# processor_main_connector.net
KiCad netlist of a schematic drawn in Altium Designer
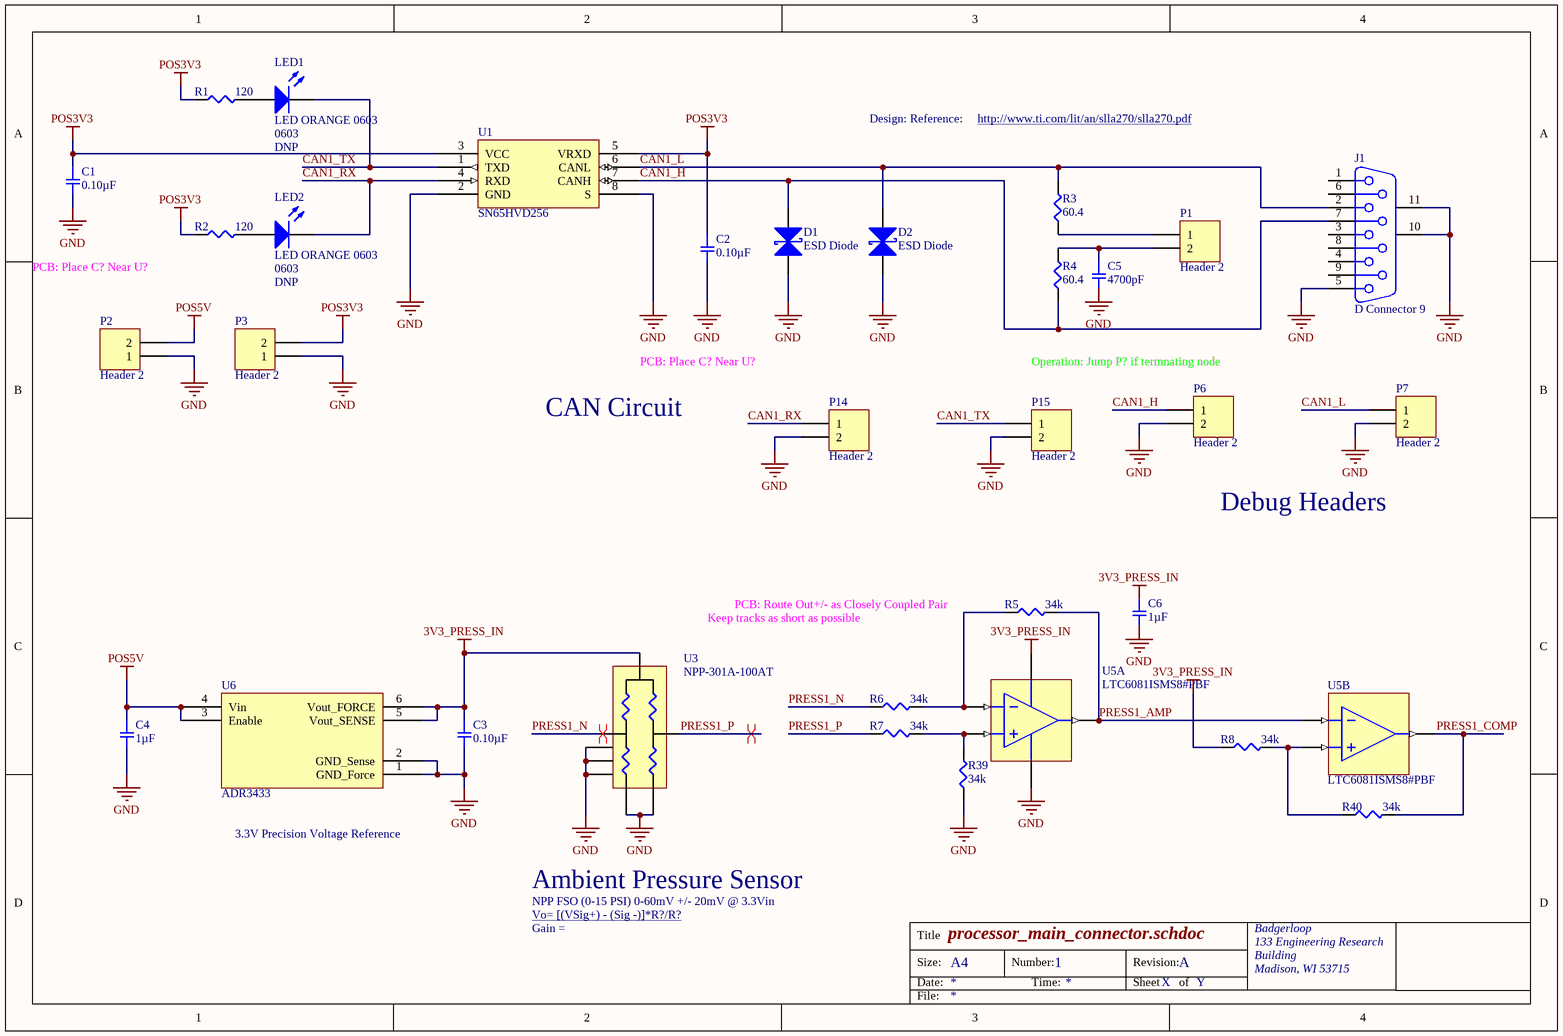
[diagram p0: processor_main_connector.SchDoc]

(export (version "E")
  (design (tool "Eeschema 10.0.6"))
  (components
    (comp (ref "C1")
      (value "0.10µF")
      (footprint "SMD-0805C")
      (description "CAP CER 0.1UF 50V X7R 0805")
      (fields
        (field (name "DIGI-KEY PART NUMBER") "490-11955-1-ND")
        (field (name "PART NUMBER") "GCD21BR71H104KA01L")
      )
      (libsource (lib "capacitor") (part "GCD21BR71H104KA01L"))
    )
    (comp (ref "C2")
      (value "0.10µF")
      (footprint "SMD-0805C")
      (description "CAP CER 0.1UF 50V X7R 0805")
      (fields
        (field (name "DIGI-KEY PART NUMBER") "490-11955-1-ND")
        (field (name "PART NUMBER") "GCD21BR71H104KA01L")
      )
      (libsource (lib "capacitor") (part "GCD21BR71H104KA01L"))
    )
    (comp (ref "C3")
      (value "0.10µF")
      (footprint "SMD-0805C")
      (description "CAP CER 0.1UF 50V X7R 0805")
      (fields
        (field (name "DIGI-KEY PART NUMBER") "490-11955-1-ND")
        (field (name "PART NUMBER") "GCD21BR71H104KA01L")
      )
      (libsource (lib "capacitor") (part "GCD21BR71H104KA01L"))
    )
    (comp (ref "C4")
      (value "1µF")
      (footprint "SMD-0805C")
      (description "CAP CER 1UF 50V X7R 0805")
      (fields
        (field (name "DIGI-KEY PART NUMBER") "490-10667-1-ND")
        (field (name "PART NUMBER") "GCJ21BR71H105KA01L")
      )
      (libsource (lib "capacitor") (part "GCJ21BR71H105KA01L"))
    )
    (comp (ref "C5")
      (value "4700pF")
      (footprint "SMD-0805C")
      (description "CAP CER 4700PF 50V NP0 0805")
      (fields
        (field (name "DIGI-KEY PART NUMBER") "490-4973-1-ND")
        (field (name "PART NUMBER") "GCM2165C1H472JA16D")
      )
      (libsource (lib "capacitor") (part "GCM2165C1H472JA16D"))
    )
    (comp (ref "C6")
      (value "1µF")
      (footprint "SMD-0805C")
      (description "CAP CER 1UF 25V X6S 0805")
      (fields
        (field (name "DIGI-KEY PART NUMBER") "490-12352-1-ND")
        (field (name "PART NUMBER") "GRT21BC81E105ME13L")
      )
      (libsource (lib "capacitor") (part "GRT21BC81E105ME13L"))
    )
    (comp (ref "D1")
      (value "ESD Diode")
      (footprint "SMD-0402-RES")
      (description "ESD Supressor")
      (fields (field (name "MANUFACTURER") "EZAEG"))
      (libsource (lib "temp") (part "ESD Diode"))
    )
    (comp (ref "D2")
      (value "ESD Diode")
      (footprint "SMD-0402-RES")
      (description "ESD Supressor")
      (fields (field (name "MANUFACTURER") "EZAEG"))
      (libsource (lib "temp") (part "ESD Diode"))
    )
    (comp (ref "J1")
      (value "D Connector 9")
      (footprint "DSUB1.385-2H9")
      (description "Receptacle Assembly, 9 Position, Right Angle")
      (fields (field (name "PUBLISHER") "Altium Limited"))
      (libsource (lib "connector") (part "D Connector 9"))
    )
    (comp (ref "LED1")
      (value "LED ORANGE 0603")
      (footprint "LED 0603 ORANGE")
      (description "A-0603UOC")
      (fields
        (field (name "MANUFACTURER") "Lighthouse LEDs")
        (field (name "PACKAGE / CASE") "0603")
        (field (name "DNP") "DNP")
      )
      (libsource (lib "misc") (part "LED ORANGE 0603"))
    )
    (comp (ref "LED2")
      (value "LED ORANGE 0603")
      (footprint "LED 0603 ORANGE")
      (description "A-0603UOC")
      (fields
        (field (name "MANUFACTURER") "Lighthouse LEDs")
        (field (name "PACKAGE / CASE") "0603")
        (field (name "DNP") "DNP")
      )
      (libsource (lib "misc") (part "LED ORANGE 0603"))
    )
    (comp (ref "P1")
      (value "Header 2")
      (footprint "Pin Header 1x2 TH Pitch 2.54mm")
      (description "Header, 2-Pin")
      (fields (field (name "PUBLISHER") "Altium Limited"))
      (libsource (lib "connector") (part "Header 2"))
    )
    (comp (ref "P2")
      (value "Header 2")
      (footprint "Pin Header 1x2 TH Pitch 2.54mm")
      (description "Header, 2-Pin")
      (fields (field (name "PUBLISHER") "Altium Limited"))
      (libsource (lib "") (part "Header 2_1"))
    )
    (comp (ref "P3")
      (value "Header 2")
      (footprint "Pin Header 1x2 TH Pitch 2.54mm")
      (description "Header, 2-Pin")
      (fields (field (name "PUBLISHER") "Altium Limited"))
      (libsource (lib "") (part "Header 2_1"))
    )
    (comp (ref "P6")
      (value "Header 2")
      (footprint "Pin Header 1x2 TH Pitch 2.54mm")
      (description "Header, 2-Pin")
      (fields (field (name "PUBLISHER") "Altium Limited"))
      (libsource (lib "connector") (part "Header 2"))
    )
    (comp (ref "P7")
      (value "Header 2")
      (footprint "Pin Header 1x2 TH Pitch 2.54mm")
      (description "Header, 2-Pin")
      (fields (field (name "PUBLISHER") "Altium Limited"))
      (libsource (lib "connector") (part "Header 2"))
    )
    (comp (ref "P14")
      (value "Header 2")
      (footprint "Pin Header 1x2 TH Pitch 2.54mm")
      (description "Header, 2-Pin")
      (fields (field (name "PUBLISHER") "Altium Limited"))
      (libsource (lib "connector") (part "Header 2"))
    )
    (comp (ref "P15")
      (value "Header 2")
      (footprint "Pin Header 1x2 TH Pitch 2.54mm")
      (description "Header, 2-Pin")
      (fields (field (name "PUBLISHER") "Altium Limited"))
      (libsource (lib "connector") (part "Header 2"))
    )
    (comp (ref "R1")
      (value "120")
      (footprint "SMD-0402-RES")
      (description "RES SMD 120 OHM 5% 1/10W 0402")
      (fields (field (name "PART NUMBER") "ERJ-2GEJ121X") (field (name "DIGI-KEY PART NUMBER") "P120JCT-ND"))
      (libsource (lib "resistor") (part "ERJ-2GEJ121X"))
    )
    (comp (ref "R2")
      (value "120")
      (footprint "SMD-0402-RES")
      (description "RES SMD 120 OHM 5% 1/10W 0402")
      (fields (field (name "PART NUMBER") "ERJ-2GEJ121X") (field (name "DIGI-KEY PART NUMBER") "P120JCT-ND"))
      (libsource (lib "resistor") (part "ERJ-2GEJ121X"))
    )
    (comp (ref "R3")
      (value "60.4")
      (footprint "SMD-0402-RES")
      (description "RES SMD 60.4 OHM 1% 1/10W 0402")
      (fields
        (field (name "PART NUMBER") "ERJ-2RKF60R4X")
        (field (name "DIGI-KEY PART NUMBER") "P60.4LCT-ND")
      )
      (libsource (lib "resistor") (part "ERJ-2RKF60R4X"))
    )
    (comp (ref "R4")
      (value "60.4")
      (footprint "SMD-0402-RES")
      (description "RES SMD 60.4 OHM 1% 1/10W 0402")
      (fields
        (field (name "PART NUMBER") "ERJ-2RKF60R4X")
        (field (name "DIGI-KEY PART NUMBER") "P60.4LCT-ND")
      )
      (libsource (lib "resistor") (part "ERJ-2RKF60R4X"))
    )
    (comp (ref "R5")
      (value "34k")
      (footprint "SMD-0402-RES")
      (description "RES SMD 34K OHM 1% 1/10W 0402")
      (fields
        (field (name "PART NUMBER") "ERJ-2RKF3402X")
        (field (name "DIGI-KEY PART NUMBER") "P34.0KLCT-ND")
      )
      (libsource (lib "resistor") (part "ERJ-2RKF3402X"))
    )
    (comp (ref "R6")
      (value "34k")
      (footprint "SMD-0402-RES")
      (description "RES SMD 34K OHM 1% 1/10W 0402")
      (fields
        (field (name "PART NUMBER") "ERJ-2RKF3402X")
        (field (name "DIGI-KEY PART NUMBER") "P34.0KLCT-ND")
      )
      (libsource (lib "resistor") (part "ERJ-2RKF3402X"))
    )
    (comp (ref "R7")
      (value "34k")
      (footprint "SMD-0402-RES")
      (description "RES SMD 34K OHM 1% 1/10W 0402")
      (fields
        (field (name "PART NUMBER") "ERJ-2RKF3402X")
        (field (name "DIGI-KEY PART NUMBER") "P34.0KLCT-ND")
      )
      (libsource (lib "resistor") (part "ERJ-2RKF3402X"))
    )
    (comp (ref "R8")
      (value "34k")
      (footprint "SMD-0402-RES")
      (description "RES SMD 34K OHM 1% 1/10W 0402")
      (fields
        (field (name "PART NUMBER") "ERJ-2RKF3402X")
        (field (name "DIGI-KEY PART NUMBER") "P34.0KLCT-ND")
      )
      (libsource (lib "resistor") (part "ERJ-2RKF3402X"))
    )
    (comp (ref "R39")
      (value "34k")
      (footprint "SMD-0402-RES")
      (description "RES SMD 34K OHM 1% 1/10W 0402")
      (fields
        (field (name "PART NUMBER") "ERJ-2RKF3402X")
        (field (name "DIGI-KEY PART NUMBER") "P34.0KLCT-ND")
      )
      (libsource (lib "resistor") (part "ERJ-2RKF3402X"))
    )
    (comp (ref "R40")
      (value "34k")
      (footprint "SMD-0402-RES")
      (description "RES SMD 34K OHM 1% 1/10W 0402")
      (fields
        (field (name "PART NUMBER") "ERJ-2RKF3402X")
        (field (name "DIGI-KEY PART NUMBER") "P34.0KLCT-ND")
      )
      (libsource (lib "resistor") (part "ERJ-2RKF3402X"))
    )
    (comp (ref "U1")
      (value "SN65HVD256")
      (footprint "SOIC127P630X175-8N")
      (description "IC TXRX CAN 5V HS 8SOIC")
      (fields (field (name "MANUFACTURER") "TI"))
      (libsource (lib "temp") (part "SN65HVD256"))
    )
    (comp (ref "U3")
      (value "NPP-301A-100AT")
      (footprint "SOIC127P610X280-8N")
      (description "SENSOR PRES 15PSIA SO8 SMD")
      (fields (field (name "MANUFACTURER") "Amphenol Advanced Sensors"))
      (libsource (lib "temp") (part "NPP-301A-100AT"))
    )
    (comp (ref "U5")
      (value "LTC6081ISMS8#PBF")
      (footprint "TSOP65P490X110-8N")
      (description "IC OPAMP GP 3.5MHZ RRO 8MSOP")
      (fields (field (name "MANUFACTURER") "Linear Technology"))
      (libsource (lib "temp") (part "LTC6081ISMS8#PBF"))
    )
    (comp (ref "U6")
      (value "ADR3433")
      (footprint "SOT95P280X145-6N")
      (description "IC VREF SERIES 3.3V SOT23-6")
      (fields (field (name "MANUFACTURER") "Analog Devices"))
      (libsource (lib "ic") (part "ADR3433"))
    )
  )
  (nets
    (net (code "1") (name "/CAN1_H") (class "Default")
      (node (ref "D1") (pin "2") (pinfunction "K_2") (pintype "passive"))
      (node (ref "J1") (pin "7") (pinfunction "7_7") (pintype "passive"))
      (node (ref "P6") (pin "1") (pinfunction "1_1") (pintype "passive"))
      (node (ref "R4") (pin "1") (pinfunction "1_1") (pintype "passive"))
      (node (ref "U1") (pin "7") (pinfunction "CANH_7") (pintype "bidirectional"))
    )
    (net (code "2") (name "/CAN1_L") (class "Default")
      (node (ref "D2") (pin "2") (pinfunction "K_2") (pintype "passive"))
      (node (ref "J1") (pin "2") (pinfunction "2_2") (pintype "passive"))
      (node (ref "P7") (pin "1") (pinfunction "1_1") (pintype "passive"))
      (node (ref "R3") (pin "2") (pinfunction "2_2") (pintype "passive"))
      (node (ref "U1") (pin "6") (pinfunction "CANL_6") (pintype "bidirectional"))
    )
    (net (code "3") (name "/CAN1_RX") (class "Default")
      (node (ref "LED2") (pin "2") (pinfunction "K_2") (pintype "passive"))
      (node (ref "P14") (pin "1") (pinfunction "1_1") (pintype "passive"))
      (node (ref "U1") (pin "4") (pinfunction "RXD_4") (pintype "input"))
    )
    (net (code "4") (name "/CAN1_TX") (class "Default")
      (node (ref "LED1") (pin "2") (pinfunction "K_2") (pintype "passive"))
      (node (ref "P15") (pin "1") (pinfunction "1_1") (pintype "passive"))
      (node (ref "U1") (pin "1") (pinfunction "TXD_1") (pintype "output"))
    )
    (net (code "5") (name "/PRESS1_AMP") (class "Default")
      (node (ref "R5") (pin "2") (pinfunction "2_2") (pintype "passive"))
      (node (ref "U5") (pin "1") (pinfunction "OUT_1") (pintype "output"))
      (node (ref "U5") (pin "6") (pinfunction "IN-_6") (pintype "input"))
    )
    (net (code "6") (name "/PRESS1_COMP") (class "Default")
      (node (ref "R40") (pin "2") (pinfunction "2_2") (pintype "passive"))
      (node (ref "U5") (pin "7") (pinfunction "OUT_7") (pintype "output"))
    )
    (net (code "7") (name "/PRESS1_N") (class "Default")
      (node (ref "R6") (pin "1") (pinfunction "1_1") (pintype "passive"))
      (node (ref "U3") (pin "2") (pinfunction "2_2") (pintype "passive"))
    )
    (net (code "8") (name "/PRESS1_P") (class "Default")
      (node (ref "R7") (pin "1") (pinfunction "1_1") (pintype "passive"))
      (node (ref "U3") (pin "6") (pinfunction "6_6") (pintype "passive"))
    )
    (net (code "9") (name "3V3_PRESS_IN") (class "Default")
      (node (ref "C3") (pin "1") (pinfunction "1_1") (pintype "passive"))
      (node (ref "C6") (pin "1") (pinfunction "1_1") (pintype "passive"))
      (node (ref "R8") (pin "1") (pinfunction "1_1") (pintype "passive"))
      (node (ref "U3") (pin "8") (pinfunction "8_8") (pintype "passive"))
      (node (ref "U5") (pin "8") (pinfunction "V+_8") (pintype "power_in"))
      (node (ref "U6") (pin "5") (pinfunction "Vout_SENSE_5") (pintype "passive"))
      (node (ref "U6") (pin "6") (pinfunction "Vout_FORCE_6") (pintype "passive"))
    )
    (net (code "10") (name "GND") (class "Default")
      (node (ref "C1") (pin "2") (pinfunction "2_2") (pintype "passive"))
      (node (ref "C2") (pin "2") (pinfunction "2_2") (pintype "passive"))
      (node (ref "C3") (pin "2") (pinfunction "2_2") (pintype "passive"))
      (node (ref "C4") (pin "2") (pinfunction "2_2") (pintype "passive"))
      (node (ref "C5") (pin "2") (pinfunction "2_2") (pintype "passive"))
      (node (ref "C6") (pin "2") (pinfunction "2_2") (pintype "passive"))
      (node (ref "D1") (pin "1") (pinfunction "A_1") (pintype "passive"))
      (node (ref "D2") (pin "1") (pinfunction "A_1") (pintype "passive"))
      (node (ref "J1") (pin "10") (pinfunction "MH1_10") (pintype "passive"))
      (node (ref "J1") (pin "11") (pinfunction "MH2_11") (pintype "passive"))
      (node (ref "J1") (pin "5") (pinfunction "5_5") (pintype "passive"))
      (node (ref "P14") (pin "2") (pinfunction "2_2") (pintype "passive"))
      (node (ref "P15") (pin "2") (pinfunction "2_2") (pintype "passive"))
      (node (ref "P2") (pin "1") (pinfunction "1_1") (pintype "passive"))
      (node (ref "P3") (pin "1") (pinfunction "1_1") (pintype "passive"))
      (node (ref "P6") (pin "2") (pinfunction "2_2") (pintype "passive"))
      (node (ref "P7") (pin "2") (pinfunction "2_2") (pintype "passive"))
      (node (ref "R39") (pin "1") (pinfunction "1_1") (pintype "passive"))
      (node (ref "U1") (pin "2") (pinfunction "GND_2") (pintype "power_in"))
      (node (ref "U1") (pin "8") (pinfunction "S_8") (pintype "passive"))
      (node (ref "U3") (pin "1") (pinfunction "1_1") (pintype "passive"))
      (node (ref "U3") (pin "3") (pinfunction "3_3") (pintype "passive"))
      (node (ref "U3") (pin "4") (pinfunction "4_4") (pintype "passive"))
      (node (ref "U3") (pin "5") (pinfunction "5_5") (pintype "passive"))
      (node (ref "U3") (pin "7") (pinfunction "7_7") (pintype "passive"))
      (node (ref "U5") (pin "4") (pinfunction "V-_4") (pintype "power_in"))
      (node (ref "U6") (pin "1") (pinfunction "GND_Force_1") (pintype "power_in"))
      (node (ref "U6") (pin "2") (pinfunction "GND_Sense_2") (pintype "power_in"))
    )
    (net (code "11") (name "Net-(C5-Pad1)") (class "Default")
      (node (ref "C5") (pin "1") (pinfunction "1_1") (pintype "passive"))
      (node (ref "P1") (pin "2") (pinfunction "2_2") (pintype "passive"))
      (node (ref "R4") (pin "2") (pinfunction "2_2") (pintype "passive"))
    )
    (net (code "12") (name "Net-(LED1-A)") (class "Default")
      (node (ref "LED1") (pin "1") (pinfunction "A_1") (pintype "passive"))
      (node (ref "R1") (pin "2") (pinfunction "2_2") (pintype "passive"))
    )
    (net (code "13") (name "Net-(LED2-A)") (class "Default")
      (node (ref "LED2") (pin "1") (pinfunction "A_1") (pintype "passive"))
      (node (ref "R2") (pin "2") (pinfunction "2_2") (pintype "passive"))
    )
    (net (code "14") (name "Net-(P1-Pad1)") (class "Default")
      (node (ref "P1") (pin "1") (pinfunction "1_1") (pintype "passive"))
      (node (ref "R3") (pin "1") (pinfunction "1_1") (pintype "passive"))
    )
    (net (code "15") (name "Net-(U5A-IN+)") (class "Default")
      (node (ref "R39") (pin "2") (pinfunction "2_2") (pintype "passive"))
      (node (ref "R7") (pin "2") (pinfunction "2_2") (pintype "passive"))
      (node (ref "U5") (pin "3") (pinfunction "IN+_3") (pintype "input"))
    )
    (net (code "16") (name "Net-(U5A-IN-)") (class "Default")
      (node (ref "R5") (pin "1") (pinfunction "1_1") (pintype "passive"))
      (node (ref "R6") (pin "2") (pinfunction "2_2") (pintype "passive"))
      (node (ref "U5") (pin "2") (pinfunction "IN-_2") (pintype "input"))
    )
    (net (code "17") (name "Net-(U5B-IN+)") (class "Default")
      (node (ref "R40") (pin "1") (pinfunction "1_1") (pintype "passive"))
      (node (ref "R8") (pin "2") (pinfunction "2_2") (pintype "passive"))
      (node (ref "U5") (pin "5") (pinfunction "IN+_5") (pintype "input"))
    )
    (net (code "18") (name "POS3V3") (class "Default")
      (node (ref "C1") (pin "1") (pinfunction "1_1") (pintype "passive"))
      (node (ref "C2") (pin "1") (pinfunction "1_1") (pintype "passive"))
      (node (ref "P3") (pin "2") (pinfunction "2_2") (pintype "passive"))
      (node (ref "R1") (pin "1") (pinfunction "1_1") (pintype "passive"))
      (node (ref "R2") (pin "1") (pinfunction "1_1") (pintype "passive"))
      (node (ref "U1") (pin "3") (pinfunction "VCC_3") (pintype "power_in"))
      (node (ref "U1") (pin "5") (pinfunction "VRXD_5") (pintype "power_in"))
    )
    (net (code "19") (name "POS5V") (class "Default")
      (node (ref "C4") (pin "1") (pinfunction "1_1") (pintype "passive"))
      (node (ref "P2") (pin "2") (pinfunction "2_2") (pintype "passive"))
      (node (ref "U6") (pin "3") (pinfunction "Enable_3") (pintype "passive"))
      (node (ref "U6") (pin "4") (pinfunction "Vin_4") (pintype "passive"))
    )
    (net (code "20") (name "unconnected-(J1-Pad1)") (class "Default")
      (node (ref "J1") (pin "1") (pinfunction "1_1") (pintype "passive"))
    )
    (net (code "21") (name "unconnected-(J1-Pad3)") (class "Default")
      (node (ref "J1") (pin "3") (pinfunction "3_3") (pintype "passive"))
    )
    (net (code "22") (name "unconnected-(J1-Pad4)") (class "Default")
      (node (ref "J1") (pin "4") (pinfunction "4_4") (pintype "passive"))
    )
    (net (code "23") (name "unconnected-(J1-Pad6)") (class "Default")
      (node (ref "J1") (pin "6") (pinfunction "6_6") (pintype "passive"))
    )
    (net (code "24") (name "unconnected-(J1-Pad8)") (class "Default")
      (node (ref "J1") (pin "8") (pinfunction "8_8") (pintype "passive"))
    )
    (net (code "25") (name "unconnected-(J1-Pad9)") (class "Default")
      (node (ref "J1") (pin "9") (pinfunction "9_9") (pintype "passive"))
    )
  )
)
